# HackflightBrushed.net
KiCad netlist of a schematic drawn in EAGLE
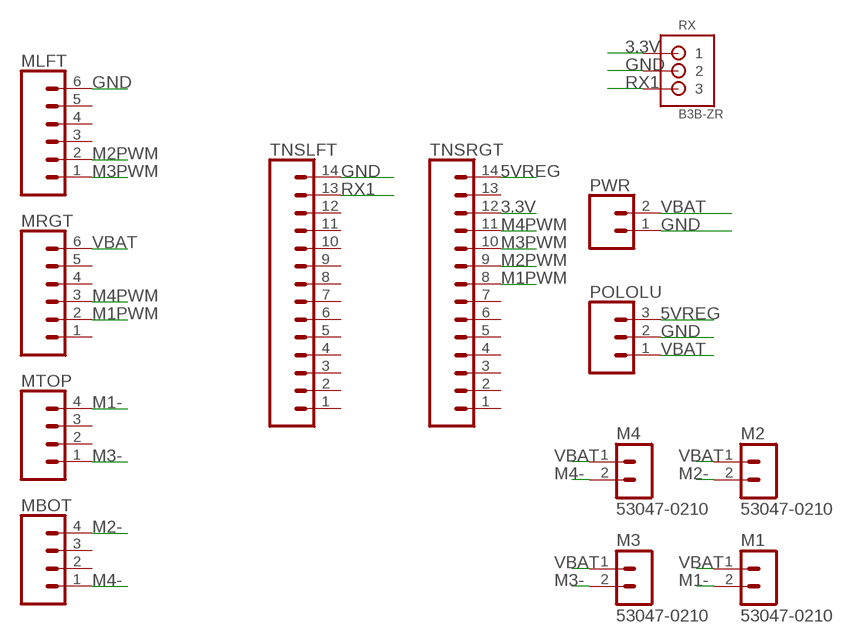
[diagram p0: schematic, sheet 1]

(export (version "E")
  (design (tool "Eeschema 10.0.6"))
  (components
    (comp (ref "M1")
      (value "53047-0210")
      (footprint "eagle-import:53047-0210")
      (libsource (lib "eagle-import") (part "53047-0210"))
    )
    (comp (ref "M2")
      (value "53047-0210")
      (footprint "eagle-import:53047-0210")
      (libsource (lib "eagle-import") (part "53047-0210"))
    )
    (comp (ref "M3")
      (value "53047-0210")
      (footprint "eagle-import:53047-0210")
      (libsource (lib "eagle-import") (part "53047-0210"))
    )
    (comp (ref "M4")
      (value "53047-0210")
      (footprint "eagle-import:53047-0210")
      (libsource (lib "eagle-import") (part "53047-0210"))
    )
    (comp (ref "MBOT")
      (value "CONN_04")
      (footprint "eagle-import:1X04")
      (libsource (lib "eagle-import") (part "CONN_04"))
    )
    (comp (ref "MLFT")
      (value "CONN_06NO_SILK_FEMALE_PTH")
      (footprint "eagle-import:1X06_NO_SILK")
      (libsource (lib "eagle-import") (part "CONN_06NO_SILK_FEMALE_PTH"))
    )
    (comp (ref "MRGT")
      (value "CONN_06NO_SILK_FEMALE_PTH")
      (footprint "eagle-import:1X06_NO_SILK")
      (libsource (lib "eagle-import") (part "CONN_06NO_SILK_FEMALE_PTH"))
    )
    (comp (ref "MTOP")
      (value "CONN_04")
      (footprint "eagle-import:1X04")
      (libsource (lib "eagle-import") (part "CONN_04"))
    )
    (comp (ref "POLOLU")
      (value "CONN_03")
      (footprint "eagle-import:1X03")
      (libsource (lib "eagle-import") (part "CONN_03"))
    )
    (comp (ref "PWR")
      (value "CONN_02")
      (footprint "eagle-import:1X02")
      (libsource (lib "eagle-import") (part "CONN_02"))
    )
    (comp (ref "RX")
      (value "B3B-ZR")
      (footprint "eagle-import:B3B-ZR")
      (libsource (lib "eagle-import") (part "B3B-ZR"))
    )
    (comp (ref "TNSLFT")
      (value "CONN_14")
      (footprint "eagle-import:1X14")
      (libsource (lib "eagle-import") (part "CONN_14"))
    )
    (comp (ref "TNSRGT")
      (value "CONN_14")
      (footprint "eagle-import:1X14")
      (libsource (lib "eagle-import") (part "CONN_14"))
    )
  )
  (nets
    (net (code "1") (name "/3.3V") (class "Default")
      (node (ref "RX") (pin "1") (pinfunction "1_1") (pintype "bidirectional"))
      (node (ref "TNSRGT") (pin "12") (pinfunction "12_12") (pintype "passive"))
    )
    (net (code "2") (name "/5VREG") (class "Default")
      (node (ref "POLOLU") (pin "3") (pinfunction "3_3") (pintype "passive"))
      (node (ref "TNSRGT") (pin "14") (pinfunction "14_14") (pintype "passive"))
    )
    (net (code "3") (name "/GND") (class "Default")
      (node (ref "MLFT") (pin "6") (pinfunction "6_6") (pintype "passive"))
      (node (ref "POLOLU") (pin "2") (pinfunction "2_2") (pintype "passive"))
      (node (ref "PWR") (pin "1") (pinfunction "1_1") (pintype "passive"))
      (node (ref "RX") (pin "2") (pinfunction "2_2") (pintype "bidirectional"))
      (node (ref "TNSLFT") (pin "14") (pinfunction "14_14") (pintype "passive"))
    )
    (net (code "4") (name "/M1-") (class "Default")
      (node (ref "M1") (pin "2") (pinfunction "2_2") (pintype "passive"))
      (node (ref "MTOP") (pin "4") (pinfunction "4_4") (pintype "passive"))
    )
    (net (code "5") (name "/M1PWM") (class "Default")
      (node (ref "MRGT") (pin "2") (pinfunction "2_2") (pintype "passive"))
      (node (ref "TNSRGT") (pin "8") (pinfunction "8_8") (pintype "passive"))
    )
    (net (code "6") (name "/M2-") (class "Default")
      (node (ref "M2") (pin "2") (pinfunction "2_2") (pintype "passive"))
      (node (ref "MBOT") (pin "4") (pinfunction "4_4") (pintype "passive"))
    )
    (net (code "7") (name "/M2PWM") (class "Default")
      (node (ref "MLFT") (pin "2") (pinfunction "2_2") (pintype "passive"))
      (node (ref "TNSRGT") (pin "9") (pinfunction "9_9") (pintype "passive"))
    )
    (net (code "8") (name "/M3-") (class "Default")
      (node (ref "M3") (pin "2") (pinfunction "2_2") (pintype "passive"))
      (node (ref "MTOP") (pin "1") (pinfunction "1_1") (pintype "passive"))
    )
    (net (code "9") (name "/M3PWM") (class "Default")
      (node (ref "MLFT") (pin "1") (pinfunction "1_1") (pintype "passive"))
      (node (ref "TNSRGT") (pin "10") (pinfunction "10_10") (pintype "passive"))
    )
    (net (code "10") (name "/M4-") (class "Default")
      (node (ref "M4") (pin "2") (pinfunction "2_2") (pintype "passive"))
      (node (ref "MBOT") (pin "1") (pinfunction "1_1") (pintype "passive"))
    )
    (net (code "11") (name "/M4PWM") (class "Default")
      (node (ref "MRGT") (pin "3") (pinfunction "3_3") (pintype "passive"))
      (node (ref "TNSRGT") (pin "11") (pinfunction "11_11") (pintype "passive"))
    )
    (net (code "12") (name "/RX1") (class "Default")
      (node (ref "RX") (pin "3") (pinfunction "3_3") (pintype "bidirectional"))
      (node (ref "TNSLFT") (pin "13") (pinfunction "13_13") (pintype "passive"))
    )
    (net (code "13") (name "/VBAT") (class "Default")
      (node (ref "M1") (pin "1") (pinfunction "1_1") (pintype "passive"))
      (node (ref "M2") (pin "1") (pinfunction "1_1") (pintype "passive"))
      (node (ref "M3") (pin "1") (pinfunction "1_1") (pintype "passive"))
      (node (ref "M4") (pin "1") (pinfunction "1_1") (pintype "passive"))
      (node (ref "MRGT") (pin "6") (pinfunction "6_6") (pintype "passive"))
      (node (ref "POLOLU") (pin "1") (pinfunction "1_1") (pintype "passive"))
      (node (ref "PWR") (pin "2") (pinfunction "2_2") (pintype "passive"))
    )
    (net (code "14") (name "unconnected-(MBOT-Pad2)") (class "Default")
      (node (ref "MBOT") (pin "2") (pinfunction "2_2") (pintype "passive"))
    )
    (net (code "15") (name "unconnected-(MBOT-Pad3)") (class "Default")
      (node (ref "MBOT") (pin "3") (pinfunction "3_3") (pintype "passive"))
    )
    (net (code "16") (name "unconnected-(MLFT-Pad3)") (class "Default")
      (node (ref "MLFT") (pin "3") (pinfunction "3_3") (pintype "passive"))
    )
    (net (code "17") (name "unconnected-(MLFT-Pad4)") (class "Default")
      (node (ref "MLFT") (pin "4") (pinfunction "4_4") (pintype "passive"))
    )
    (net (code "18") (name "unconnected-(MLFT-Pad5)") (class "Default")
      (node (ref "MLFT") (pin "5") (pinfunction "5_5") (pintype "passive"))
    )
    (net (code "19") (name "unconnected-(MRGT-Pad1)") (class "Default")
      (node (ref "MRGT") (pin "1") (pinfunction "1_1") (pintype "passive"))
    )
    (net (code "20") (name "unconnected-(MRGT-Pad4)") (class "Default")
      (node (ref "MRGT") (pin "4") (pinfunction "4_4") (pintype "passive"))
    )
    (net (code "21") (name "unconnected-(MRGT-Pad5)") (class "Default")
      (node (ref "MRGT") (pin "5") (pinfunction "5_5") (pintype "passive"))
    )
    (net (code "22") (name "unconnected-(MTOP-Pad2)") (class "Default")
      (node (ref "MTOP") (pin "2") (pinfunction "2_2") (pintype "passive"))
    )
    (net (code "23") (name "unconnected-(MTOP-Pad3)") (class "Default")
      (node (ref "MTOP") (pin "3") (pinfunction "3_3") (pintype "passive"))
    )
    (net (code "24") (name "unconnected-(TNSLFT-Pad1)") (class "Default")
      (node (ref "TNSLFT") (pin "1") (pinfunction "1_1") (pintype "passive"))
    )
    (net (code "25") (name "unconnected-(TNSLFT-Pad2)") (class "Default")
      (node (ref "TNSLFT") (pin "2") (pinfunction "2_2") (pintype "passive"))
    )
    (net (code "26") (name "unconnected-(TNSLFT-Pad3)") (class "Default")
      (node (ref "TNSLFT") (pin "3") (pinfunction "3_3") (pintype "passive"))
    )
    (net (code "27") (name "unconnected-(TNSLFT-Pad4)") (class "Default")
      (node (ref "TNSLFT") (pin "4") (pinfunction "4_4") (pintype "passive"))
    )
    (net (code "28") (name "unconnected-(TNSLFT-Pad5)") (class "Default")
      (node (ref "TNSLFT") (pin "5") (pinfunction "5_5") (pintype "passive"))
    )
    (net (code "29") (name "unconnected-(TNSLFT-Pad6)") (class "Default")
      (node (ref "TNSLFT") (pin "6") (pinfunction "6_6") (pintype "passive"))
    )
    (net (code "30") (name "unconnected-(TNSLFT-Pad7)") (class "Default")
      (node (ref "TNSLFT") (pin "7") (pinfunction "7_7") (pintype "passive"))
    )
    (net (code "31") (name "unconnected-(TNSLFT-Pad8)") (class "Default")
      (node (ref "TNSLFT") (pin "8") (pinfunction "8_8") (pintype "passive"))
    )
    (net (code "32") (name "unconnected-(TNSLFT-Pad9)") (class "Default")
      (node (ref "TNSLFT") (pin "9") (pinfunction "9_9") (pintype "passive"))
    )
    (net (code "33") (name "unconnected-(TNSLFT-Pad10)") (class "Default")
      (node (ref "TNSLFT") (pin "10") (pinfunction "10_10") (pintype "passive"))
    )
    (net (code "34") (name "unconnected-(TNSLFT-Pad11)") (class "Default")
      (node (ref "TNSLFT") (pin "11") (pinfunction "11_11") (pintype "passive"))
    )
    (net (code "35") (name "unconnected-(TNSLFT-Pad12)") (class "Default")
      (node (ref "TNSLFT") (pin "12") (pinfunction "12_12") (pintype "passive"))
    )
    (net (code "36") (name "unconnected-(TNSRGT-Pad1)") (class "Default")
      (node (ref "TNSRGT") (pin "1") (pinfunction "1_1") (pintype "passive"))
    )
    (net (code "37") (name "unconnected-(TNSRGT-Pad2)") (class "Default")
      (node (ref "TNSRGT") (pin "2") (pinfunction "2_2") (pintype "passive"))
    )
    (net (code "38") (name "unconnected-(TNSRGT-Pad3)") (class "Default")
      (node (ref "TNSRGT") (pin "3") (pinfunction "3_3") (pintype "passive"))
    )
    (net (code "39") (name "unconnected-(TNSRGT-Pad4)") (class "Default")
      (node (ref "TNSRGT") (pin "4") (pinfunction "4_4") (pintype "passive"))
    )
    (net (code "40") (name "unconnected-(TNSRGT-Pad5)") (class "Default")
      (node (ref "TNSRGT") (pin "5") (pinfunction "5_5") (pintype "passive"))
    )
    (net (code "41") (name "unconnected-(TNSRGT-Pad6)") (class "Default")
      (node (ref "TNSRGT") (pin "6") (pinfunction "6_6") (pintype "passive"))
    )
    (net (code "42") (name "unconnected-(TNSRGT-Pad7)") (class "Default")
      (node (ref "TNSRGT") (pin "7") (pinfunction "7_7") (pintype "passive"))
    )
    (net (code "43") (name "unconnected-(TNSRGT-Pad13)") (class "Default")
      (node (ref "TNSRGT") (pin "13") (pinfunction "13_13") (pintype "passive"))
    )
  )
)
